# RTI-RoR.net
KiCad netlist of a schematic drawn in EAGLE
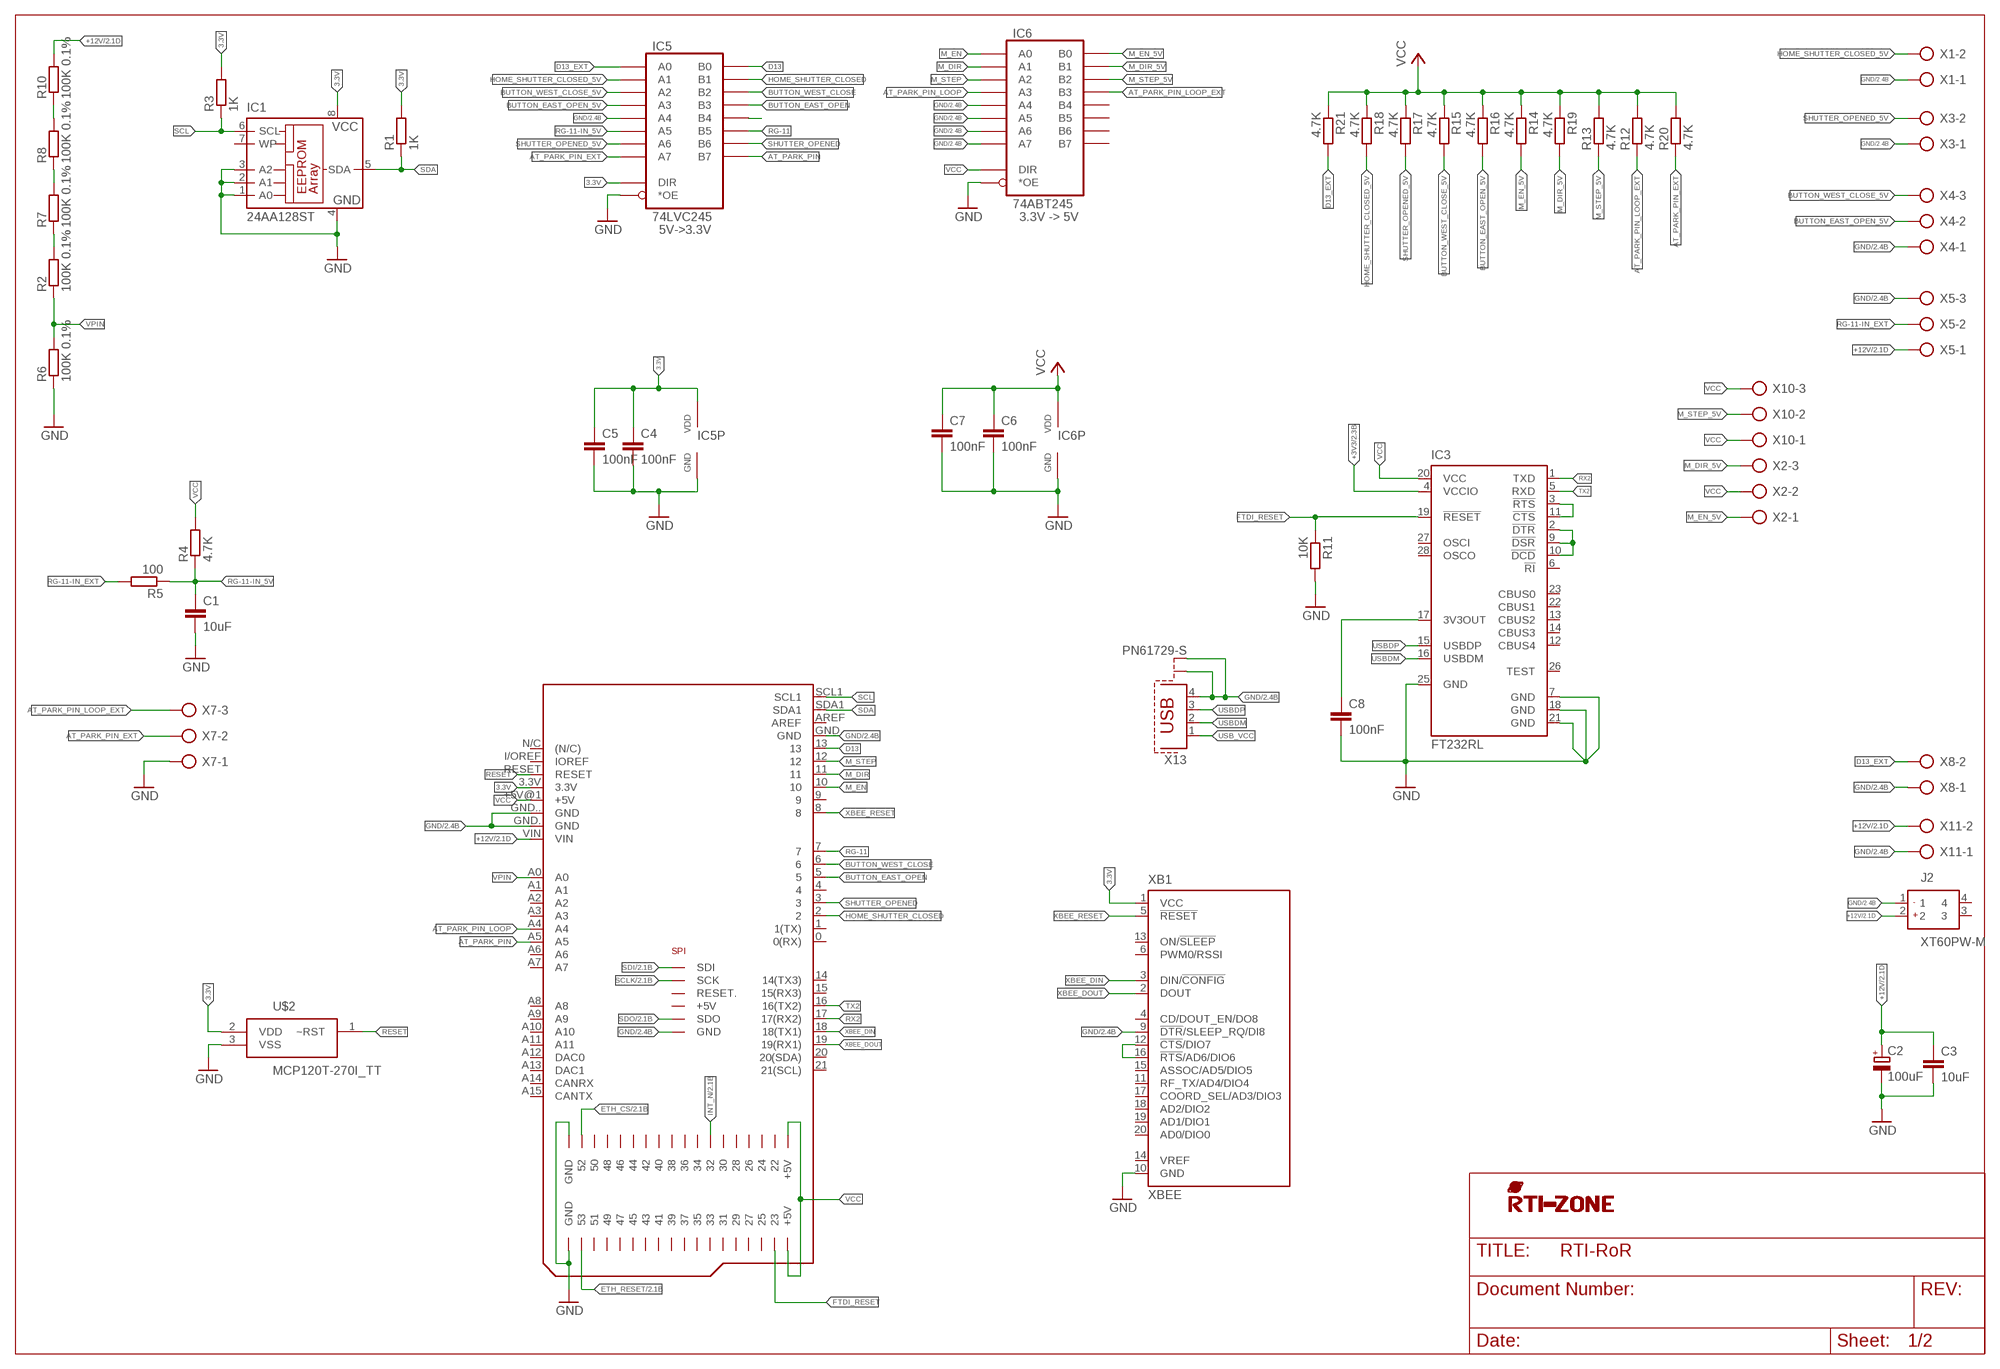
[diagram p0: schematic, sheet 1]
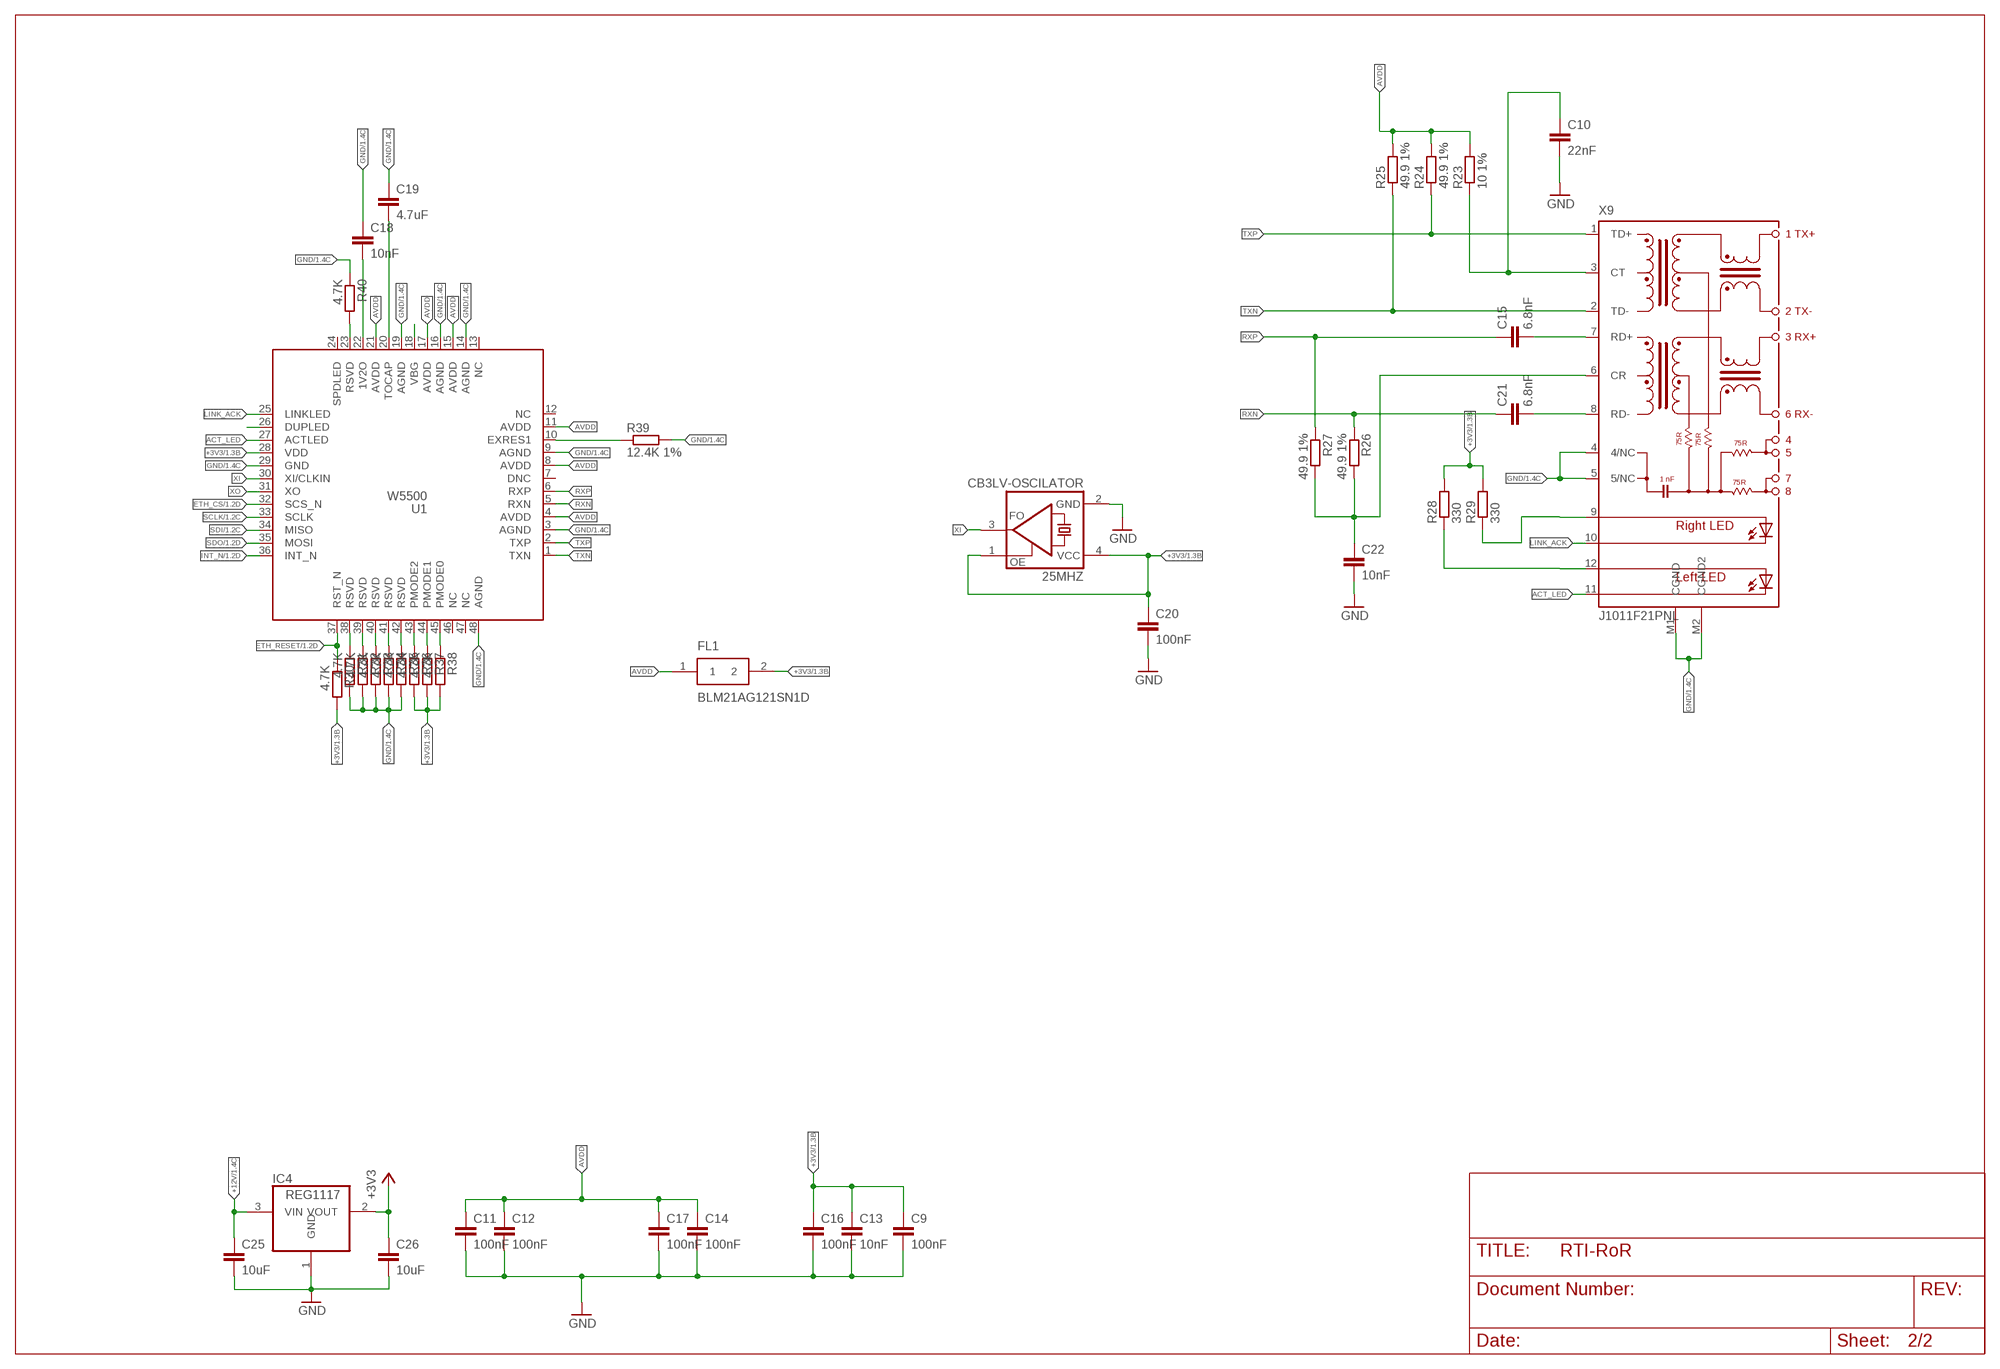
[diagram p1: schematic, sheet 2]

(export (version "E")
  (design (tool "Eeschema 10.0.6"))
  (components
    (comp (ref "C1")
      (value "10uF")
      (footprint "eagle-import:C0805")
      (fields (field (name "MPN") "CC0805KKX5R8BB106"))
      (libsource (lib "eagle-import") (part "C-EUC0805"))
    )
    (comp (ref "C2")
      (value "100uF")
      (footprint "eagle-import:UD-10X10_NICHICON")
      (fields (field (name "MPN") "MAL215099804E3"))
      (libsource (lib "eagle-import") (part "CPOL-EUUD-10X10"))
    )
    (comp (ref "C3")
      (value "10uF")
      (footprint "eagle-import:C0805")
      (fields (field (name "MPN") "CC0805KKX5R8BB106"))
      (libsource (lib "eagle-import") (part "C-EUC0805"))
    )
    (comp (ref "C4")
      (value "100nF")
      (footprint "eagle-import:C0805")
      (fields (field (name "MPN") "0805YD104KAT2A"))
      (libsource (lib "eagle-import") (part "C-EUC0805"))
    )
    (comp (ref "C5")
      (value "100nF")
      (footprint "eagle-import:C0805")
      (fields (field (name "MPN") "0805YD104KAT2A"))
      (libsource (lib "eagle-import") (part "C-EUC0805"))
    )
    (comp (ref "C6")
      (value "100nF")
      (footprint "eagle-import:C0805")
      (fields (field (name "MPN") "0805YD104KAT2A"))
      (libsource (lib "eagle-import") (part "C-EUC0805"))
    )
    (comp (ref "C7")
      (value "100nF")
      (footprint "eagle-import:C0805")
      (fields (field (name "MPN") "0805YD104KAT2A"))
      (libsource (lib "eagle-import") (part "C-EUC0805"))
    )
    (comp (ref "C8")
      (value "100nF")
      (footprint "eagle-import:C0805")
      (fields (field (name "MPN") "0805YD104KAT2A"))
      (libsource (lib "eagle-import") (part "C-EUC0805"))
    )
    (comp (ref "IC1")
      (value "24AA128ST")
      (footprint "eagle-import:TSSOP8")
      (fields (field (name "MF") "MICROCHIP") (field (name "MPN") "24AA128-I/ST"))
      (libsource (lib "eagle-import") (part "24STAA128"))
    )
    (comp (ref "IC3")
      (value "FT232RL")
      (footprint "eagle-import:SSOP28")
      (fields (field (name "MPN") "FT232RL-REEL"))
      (libsource (lib "eagle-import") (part "FT232RL"))
    )
    (comp (ref "IC5")
      (value "74LVC245")
      (footprint "eagle-import:TSSOP20")
      (fields (field (name "MPN") "74LVC245APW,112"))
      (libsource (lib "eagle-import") (part "74245LVC"))
    )
    (comp (ref "IC6")
      (value "74ABT245")
      (footprint "eagle-import:TSSOP20")
      (fields (field (name "MPN") "74ABT245PW,112"))
      (libsource (lib "eagle-import") (part "74245ABT"))
    )
    (comp (ref "J2")
      (value "XT60PW-M")
      (footprint "eagle-import:XT60PWM")
      (libsource (lib "eagle-import") (part "XT60PW-M"))
    )
    (comp (ref "R1")
      (value "1K")
      (footprint "eagle-import:R0805")
      (fields (field (name "MPN") "RT0805FRE071KL"))
      (libsource (lib "eagle-import") (part "R-EU_R0805"))
    )
    (comp (ref "R2")
      (value "100K 0.1%")
      (footprint "eagle-import:R0805")
      (fields (field (name "MPN") "AT0805BRD07100KL"))
      (libsource (lib "eagle-import") (part "R-EU_R0805"))
    )
    (comp (ref "R3")
      (value "1K")
      (footprint "eagle-import:R0805")
      (fields (field (name "MPN") "RT0805FRE071KL"))
      (libsource (lib "eagle-import") (part "R-EU_R0805"))
    )
    (comp (ref "R4")
      (value "4.7K")
      (footprint "eagle-import:R0805")
      (fields (field (name "MPN") "RT0805FRE074K7L"))
      (libsource (lib "eagle-import") (part "R-EU_R0805"))
    )
    (comp (ref "R5")
      (value "100")
      (footprint "eagle-import:R0805")
      (fields (field (name "MPN") "RT0805FRD07100RL"))
      (libsource (lib "eagle-import") (part "R-EU_R0805"))
    )
    (comp (ref "R6")
      (value "100K 0.1%")
      (footprint "eagle-import:R0805")
      (fields (field (name "MPN") "AT0805BRD07100KL"))
      (libsource (lib "eagle-import") (part "R-EU_R0805"))
    )
    (comp (ref "R7")
      (value "100K 0.1%")
      (footprint "eagle-import:R0805")
      (fields (field (name "MPN") "AT0805BRD07100KL"))
      (libsource (lib "eagle-import") (part "R-EU_R0805"))
    )
    (comp (ref "R8")
      (value "100K 0.1%")
      (footprint "eagle-import:R0805")
      (fields (field (name "MPN") "AT0805BRD07100KL"))
      (libsource (lib "eagle-import") (part "R-EU_R0805"))
    )
    (comp (ref "R10")
      (value "100K 0.1%")
      (footprint "eagle-import:R0805")
      (fields (field (name "MPN") "AT0805BRD07100KL"))
      (libsource (lib "eagle-import") (part "R-EU_R0805"))
    )
    (comp (ref "R11")
      (value "10K")
      (footprint "eagle-import:R0805")
      (fields (field (name "MPN") "RT0805FRE0710KL"))
      (libsource (lib "eagle-import") (part "R-EU_R0805"))
    )
    (comp (ref "R12")
      (value "4.7K")
      (footprint "eagle-import:R0805")
      (fields (field (name "MPN") "RT0805FRE074K7L"))
      (libsource (lib "eagle-import") (part "R-EU_R0805"))
    )
    (comp (ref "R13")
      (value "4.7K")
      (footprint "eagle-import:R0805")
      (fields (field (name "MPN") "RT0805FRE074K7L"))
      (libsource (lib "eagle-import") (part "R-EU_R0805"))
    )
    (comp (ref "R14")
      (value "4.7K")
      (footprint "eagle-import:R0805")
      (fields (field (name "MPN") "RT0805FRE074K7L"))
      (libsource (lib "eagle-import") (part "R-EU_R0805"))
    )
    (comp (ref "R15")
      (value "4.7K")
      (footprint "eagle-import:R0805")
      (fields (field (name "MPN") "RT0805FRE074K7L"))
      (libsource (lib "eagle-import") (part "R-EU_R0805"))
    )
    (comp (ref "R16")
      (value "4.7K")
      (footprint "eagle-import:R0805")
      (fields (field (name "MPN") "RT0805FRE074K7L"))
      (libsource (lib "eagle-import") (part "R-EU_R0805"))
    )
    (comp (ref "R17")
      (value "4.7K")
      (footprint "eagle-import:R0805")
      (fields (field (name "MPN") "RT0805FRE074K7L"))
      (libsource (lib "eagle-import") (part "R-EU_R0805"))
    )
    (comp (ref "R18")
      (value "4.7K")
      (footprint "eagle-import:R0805")
      (fields (field (name "MPN") "RT0805FRE074K7L"))
      (libsource (lib "eagle-import") (part "R-EU_R0805"))
    )
    (comp (ref "R19")
      (value "4.7K")
      (footprint "eagle-import:R0805")
      (fields (field (name "MPN") "RT0805FRE074K7L"))
      (libsource (lib "eagle-import") (part "R-EU_R0805"))
    )
    (comp (ref "R20")
      (value "4.7K")
      (footprint "eagle-import:R0805")
      (fields (field (name "MPN") "RT0805FRE074K7L"))
      (libsource (lib "eagle-import") (part "R-EU_R0805"))
    )
    (comp (ref "R21")
      (value "4.7K")
      (footprint "eagle-import:R0805")
      (fields (field (name "MPN") "RT0805FRE074K7L"))
      (libsource (lib "eagle-import") (part "R-EU_R0805"))
    )
    (comp (ref "U$1")
      (value "ARDUINO_DUE_SHIELD_FULL")
      (footprint "eagle-import:ARDUINO_DUE_SHIELD_FULL")
      (libsource (lib "eagle-import") (part "ARDUINO_DUE_SHIELD_FULL"))
    )
    (comp (ref "U$2")
      (value "MCP120T-270I_TT")
      (footprint "eagle-import:SOT95P237X112-3N")
      (fields
        (field (name "MANUFACTURER_PART_NUMBER") "MCP120T-270I/TT")
        (field (name "MOUSER_PART_NUMBER") "579-MCP120T-270I/TT")
      )
      (libsource (lib "eagle-import") (part "MCP120T-270I_TT"))
    )
    (comp (ref "U$4")
      (value "RTI-LOGO_BIG")
      (footprint "eagle-import:LOGO_BIG")
      (libsource (lib "eagle-import") (part "RTI-LOGO_BIG"))
    )
    (comp (ref "X1")
      (value "AK500/2")
      (footprint "eagle-import:AK500_2")
      (fields (field (name "MPN") "691101710002"))
      (libsource (lib "eagle-import") (part "AK500/2"))
    )
    (comp (ref "X2")
      (value "AK500/3")
      (footprint "eagle-import:AK500_3")
      (libsource (lib "eagle-import") (part "AK500/3"))
    )
    (comp (ref "X3")
      (value "AK500/2")
      (footprint "eagle-import:AK500_2")
      (fields (field (name "MPN") "691101710002"))
      (libsource (lib "eagle-import") (part "AK500/2"))
    )
    (comp (ref "X4")
      (value "AK500/3")
      (footprint "eagle-import:AK500_3")
      (fields (field (name "MPN") "691101710003"))
      (libsource (lib "eagle-import") (part "AK500/3"))
    )
    (comp (ref "X5")
      (value "AK500/3")
      (footprint "eagle-import:AK500_3")
      (fields (field (name "MPN") "691101710003"))
      (libsource (lib "eagle-import") (part "AK500/3"))
    )
    (comp (ref "X7")
      (value "AK500/3")
      (footprint "eagle-import:AK500_3")
      (fields (field (name "MPN") "691101710003"))
      (libsource (lib "eagle-import") (part "AK500/3"))
    )
    (comp (ref "X8")
      (value "AK500/2")
      (footprint "eagle-import:AK500_2")
      (fields (field (name "MPN") "691101710002"))
      (libsource (lib "eagle-import") (part "AK500/2"))
    )
    (comp (ref "X10")
      (value "AK500/3")
      (footprint "eagle-import:AK500_3")
      (libsource (lib "eagle-import") (part "AK500/3"))
    )
    (comp (ref "X11")
      (value "AK500/2")
      (footprint "eagle-import:AK500_2")
      (fields (field (name "MPN") "691101710002"))
      (libsource (lib "eagle-import") (part "AK500/2"))
    )
    (comp (ref "X13")
      (value "PN61729-S")
      (footprint "eagle-import:PN61729-S")
      (fields (field (name "MPN") "SS-52300-001"))
      (libsource (lib "eagle-import") (part "PN61729-S"))
    )
    (comp (ref "XB1")
      (value "XBEE")
      (footprint "eagle-import:XBEE")
      (fields (field (name "MPN") "XBP24-Z7UIT-004"))
      (libsource (lib "eagle-import") (part "XBEE"))
    )
    (comp (ref "25MHZ")
      (value "CB3LV-OSCILATOR")
      (footprint "eagle-import:SMD-7050_4P")
      (fields (field (name "MPN") "CB3LV-3I-25M0000"))
      (libsource (lib "eagle-import") (part "CB3LV-OSCILATOR"))
    )
    (comp (ref "C9")
      (value "100nF")
      (footprint "eagle-import:C0805")
      (fields (field (name "MPN") "0805YD104KAT2A"))
      (libsource (lib "eagle-import") (part "C-EUC0805"))
    )
    (comp (ref "C10")
      (value "22nF")
      (footprint "eagle-import:C0805")
      (fields (field (name "MPN") "CC0805JRX7R8BB223"))
      (libsource (lib "eagle-import") (part "C-EUC0805"))
    )
    (comp (ref "C11")
      (value "100nF")
      (footprint "eagle-import:C0805")
      (fields (field (name "MPN") "0805YD104KAT2A"))
      (libsource (lib "eagle-import") (part "C-EUC0805"))
    )
    (comp (ref "C12")
      (value "100nF")
      (footprint "eagle-import:C0805")
      (fields (field (name "MPN") "0805YD104KAT2A"))
      (libsource (lib "eagle-import") (part "C-EUC0805"))
    )
    (comp (ref "C13")
      (value "10nF")
      (footprint "eagle-import:C0805")
      (fields (field (name "MPN") " CC0805KRX7R9BB103"))
      (libsource (lib "eagle-import") (part "C-EUC0805"))
    )
    (comp (ref "C14")
      (value "100nF")
      (footprint "eagle-import:C0805")
      (fields (field (name "MPN") "0805YD104KAT2A"))
      (libsource (lib "eagle-import") (part "C-EUC0805"))
    )
    (comp (ref "C15")
      (value "6.8nF")
      (footprint "eagle-import:C0805")
      (fields (field (name "MPN") "C0805C682F4HACTU"))
      (libsource (lib "eagle-import") (part "C-EUC0805"))
    )
    (comp (ref "C16")
      (value "100nF")
      (footprint "eagle-import:C0805")
      (fields (field (name "MPN") "0805YD104KAT2A"))
      (libsource (lib "eagle-import") (part "C-EUC0805"))
    )
    (comp (ref "C17")
      (value "100nF")
      (footprint "eagle-import:C0805")
      (fields (field (name "MPN") "0805YD104KAT2A"))
      (libsource (lib "eagle-import") (part "C-EUC0805"))
    )
    (comp (ref "C18")
      (value "10nF")
      (footprint "eagle-import:C0805")
      (fields (field (name "MPN") " CC0805KRX7R9BB103"))
      (libsource (lib "eagle-import") (part "C-EUC0805"))
    )
    (comp (ref "C19")
      (value "4.7uF")
      (footprint "eagle-import:C0805")
      (fields (field (name "MPN") "C0805C475J3RACTU"))
      (libsource (lib "eagle-import") (part "C-EUC0805"))
    )
    (comp (ref "C20")
      (value "100nF")
      (footprint "eagle-import:C0805")
      (fields (field (name "MPN") "0805YD104KAT2A"))
      (libsource (lib "eagle-import") (part "C-EUC0805"))
    )
    (comp (ref "C21")
      (value "6.8nF")
      (footprint "eagle-import:C0805")
      (fields (field (name "MPN") "C0805C682F4HACTU"))
      (libsource (lib "eagle-import") (part "C-EUC0805"))
    )
    (comp (ref "C22")
      (value "10nF")
      (footprint "eagle-import:C0805")
      (fields (field (name "MPN") " CC0805KRX7R9BB103"))
      (libsource (lib "eagle-import") (part "C-EUC0805"))
    )
    (comp (ref "C25")
      (value "10uF")
      (footprint "eagle-import:C0805")
      (fields (field (name "MPN") "CC0805KKX5R8BB106"))
      (libsource (lib "eagle-import") (part "C-EUC0805"))
    )
    (comp (ref "C26")
      (value "10uF")
      (footprint "eagle-import:C0805")
      (fields (field (name "MPN") "CC0805KKX5R8BB106"))
      (libsource (lib "eagle-import") (part "C-EUC0805"))
    )
    (comp (ref "FL1")
      (value "BLM21AG121SN1D")
      (footprint "eagle-import:L0805")
      (libsource (lib "eagle-import") (part "BLM21AG121SN1D"))
    )
    (comp (ref "IC4")
      (value "REG1117")
      (footprint "eagle-import:SOT223")
      (fields (field (name "MPN") "REG1117-3.3/2K5"))
      (libsource (lib "eagle-import") (part "REG1117"))
    )
    (comp (ref "R23")
      (value "10 1%")
      (footprint "eagle-import:R0805")
      (fields (field (name "MPN") "RT0805FRE1310RL"))
      (libsource (lib "eagle-import") (part "R-EU_R0805"))
    )
    (comp (ref "R24")
      (value "49.9 1%")
      (footprint "eagle-import:R0805")
      (fields (field (name "MPN") "RC0805FR-0749R9L"))
      (libsource (lib "eagle-import") (part "R-EU_R0805"))
    )
    (comp (ref "R25")
      (value "49.9 1%")
      (footprint "eagle-import:R0805")
      (fields (field (name "MPN") "RC0805FR-0749R9L"))
      (libsource (lib "eagle-import") (part "R-EU_R0805"))
    )
    (comp (ref "R26")
      (value "49.9 1%")
      (footprint "eagle-import:R0805")
      (fields (field (name "MPN") "RC0805FR-0749R9L"))
      (libsource (lib "eagle-import") (part "R-EU_R0805"))
    )
    (comp (ref "R27")
      (value "49.9 1%")
      (footprint "eagle-import:R0805")
      (fields (field (name "MPN") "RC0805FR-0749R9L"))
      (libsource (lib "eagle-import") (part "R-EU_R0805"))
    )
    (comp (ref "R28")
      (value "330")
      (footprint "eagle-import:R0805")
      (fields (field (name "MPN") " RC0805JR-07330RL"))
      (libsource (lib "eagle-import") (part "R-EU_R0805"))
    )
    (comp (ref "R29")
      (value "330")
      (footprint "eagle-import:R0805")
      (fields (field (name "MPN") " RC0805JR-07330RL"))
      (libsource (lib "eagle-import") (part "R-EU_R0805"))
    )
    (comp (ref "R30")
      (value "4.7K")
      (footprint "eagle-import:R0805")
      (fields (field (name "MPN") "RT0805FRE074K7L"))
      (libsource (lib "eagle-import") (part "R-EU_R0805"))
    )
    (comp (ref "R31")
      (value "4.7K")
      (footprint "eagle-import:R0805")
      (fields (field (name "MPN") "RT0805FRE074K7L"))
      (libsource (lib "eagle-import") (part "R-EU_R0805"))
    )
    (comp (ref "R32")
      (value "4.7K")
      (footprint "eagle-import:R0805")
      (fields (field (name "MPN") "RT0805FRE074K7L"))
      (libsource (lib "eagle-import") (part "R-EU_R0805"))
    )
    (comp (ref "R33")
      (value "4.7K")
      (footprint "eagle-import:R0805")
      (fields (field (name "MPN") "RT0805FRE074K7L"))
      (libsource (lib "eagle-import") (part "R-EU_R0805"))
    )
    (comp (ref "R34")
      (value "4.7K")
      (footprint "eagle-import:R0805")
      (fields (field (name "MPN") "RT0805FRE074K7L"))
      (libsource (lib "eagle-import") (part "R-EU_R0805"))
    )
    (comp (ref "R35")
      (value "4.7K")
      (footprint "eagle-import:R0805")
      (fields (field (name "MPN") "RT0805FRE074K7L"))
      (libsource (lib "eagle-import") (part "R-EU_R0805"))
    )
    (comp (ref "R36")
      (value "4.7K")
      (footprint "eagle-import:R0805")
      (fields (field (name "MPN") "RT0805FRE074K7L"))
      (libsource (lib "eagle-import") (part "R-EU_R0805"))
    )
    (comp (ref "R37")
      (value "4.7K")
      (footprint "eagle-import:R0805")
      (fields (field (name "MPN") "RT0805FRE074K7L"))
      (libsource (lib "eagle-import") (part "R-EU_R0805"))
    )
    (comp (ref "R38")
      (value "4.7K")
      (footprint "eagle-import:R0805")
      (fields (field (name "MPN") "RT0805FRE074K7L"))
      (libsource (lib "eagle-import") (part "R-EU_R0805"))
    )
    (comp (ref "R39")
      (value "12.4K 1%")
      (footprint "eagle-import:R0805")
      (fields (field (name "MPN") "RC0805FR-0712K4L"))
      (libsource (lib "eagle-import") (part "R-EU_R0805"))
    )
    (comp (ref "R40")
      (value "4.7K")
      (footprint "eagle-import:R0805")
      (fields (field (name "MPN") "RT0805FRE074K7L"))
      (libsource (lib "eagle-import") (part "R-EU_R0805"))
    )
    (comp (ref "U1")
      (value "W5500")
      (footprint "eagle-import:LQFP48")
      (libsource (lib "eagle-import") (part "W5500"))
    )
    (comp (ref "X9")
      (value "J1011F21PNL")
      (footprint "eagle-import:J1011F21PNL")
      (fields (field (name "MPN") "J1011F21PNL"))
      (libsource (lib "eagle-import") (part "J1011F21PNL"))
    )
  )
  (nets
    (net (code "1") (name "+3V3") (class "Default")
      (node (ref "25MHZ") (pin "1") (pinfunction "OE_1") (pintype "input"))
      (node (ref "25MHZ") (pin "4") (pinfunction "VDD_4") (pintype "power_in"))
      (node (ref "C13") (pin "1") (pinfunction "1_1") (pintype "passive"))
      (node (ref "C16") (pin "1") (pinfunction "1_1") (pintype "passive"))
      (node (ref "C20") (pin "1") (pinfunction "1_1") (pintype "passive"))
      (node (ref "C26") (pin "1") (pinfunction "1_1") (pintype "passive"))
      (node (ref "C9") (pin "1") (pinfunction "1_1") (pintype "passive"))
      (node (ref "FL1") (pin "2") (pinfunction "2_2") (pintype "bidirectional"))
      (node (ref "IC3") (pin "4") (pinfunction "VCCIO_4") (pintype "power_in"))
      (node (ref "IC4") (pin "2") (pinfunction "VOUT_2") (pintype "output"))
      (node (ref "R28") (pin "2") (pinfunction "2_2") (pintype "passive"))
      (node (ref "R29") (pin "2") (pinfunction "2_2") (pintype "passive"))
      (node (ref "R30") (pin "2") (pinfunction "2_2") (pintype "passive"))
      (node (ref "R36") (pin "2") (pinfunction "2_2") (pintype "passive"))
      (node (ref "R37") (pin "2") (pinfunction "2_2") (pintype "passive"))
      (node (ref "R38") (pin "2") (pinfunction "2_2") (pintype "passive"))
      (node (ref "U1") (pin "28") (pinfunction "VDD_28") (pintype "passive"))
    )
    (net (code "2") (name "+5V") (class "Default")
      (node (ref "U$1") (pin "+5V@2") (pinfunction "+5V_+5V@2") (pintype "power_in"))
    )
    (net (code "3") (name "+12V") (class "Default")
      (node (ref "C2") (pin "+") (pinfunction "+_+") (pintype "passive"))
      (node (ref "C25") (pin "1") (pinfunction "1_1") (pintype "passive"))
      (node (ref "C3") (pin "1") (pinfunction "1_1") (pintype "passive"))
      (node (ref "IC4") (pin "3") (pinfunction "VIN_3") (pintype "input"))
      (node (ref "J2") (pin "2") (pinfunction "2_2") (pintype "bidirectional"))
      (node (ref "R10") (pin "2") (pinfunction "2_2") (pintype "passive"))
      (node (ref "U$1") (pin "VIN") (pinfunction "VIN_VIN") (pintype "power_in"))
      (node (ref "X11") (pin "2") (pinfunction "KL_2") (pintype "passive"))
      (node (ref "X5") (pin "1") (pinfunction "KL_1") (pintype "passive"))
    )
    (net (code "4") (name "3.3V") (class "Default")
      (node (ref "C4") (pin "1") (pinfunction "1_1") (pintype "passive"))
      (node (ref "C5") (pin "1") (pinfunction "1_1") (pintype "passive"))
      (node (ref "IC1") (pin "8") (pinfunction "VCC_8") (pintype "power_in"))
      (node (ref "IC5") (pin "P$1") (pinfunction "DIR_P$1") (pintype "input"))
      (node (ref "IC5") (pin "P$20") (pinfunction "VDD_P$20") (pintype "power_in"))
      (node (ref "R1") (pin "2") (pinfunction "2_2") (pintype "passive"))
      (node (ref "R3") (pin "2") (pinfunction "2_2") (pintype "passive"))
      (node (ref "U$1") (pin "3.3V") (pinfunction "3.3V_3.3V") (pintype "power_in"))
      (node (ref "U$2") (pin "2") (pinfunction "VDD_2") (pintype "bidirectional"))
      (node (ref "XB1") (pin "1") (pinfunction "VCC_1") (pintype "power_in"))
    )
    (net (code "5") (name "ACT_LED") (class "Default")
      (node (ref "U1") (pin "27") (pinfunction "ACTLED_27") (pintype "passive"))
      (node (ref "X9") (pin "11") (pinfunction "C-L_11") (pintype "passive"))
    )
    (net (code "6") (name "AT_PARK_PIN") (class "Default")
      (node (ref "IC5") (pin "P$11") (pinfunction "B7_P$11") (pintype "bidirectional"))
      (node (ref "U$1") (pin "A5") (pinfunction "A5_A5") (pintype "bidirectional"))
    )
    (net (code "7") (name "AT_PARK_PIN_EXT") (class "Default")
      (node (ref "IC5") (pin "P$9") (pinfunction "A7_P$9") (pintype "bidirectional"))
      (node (ref "R20") (pin "1") (pinfunction "1_1") (pintype "passive"))
      (node (ref "X7") (pin "2") (pinfunction "KL_2") (pintype "passive"))
    )
    (net (code "8") (name "AT_PARK_PIN_LOOP") (class "Default")
      (node (ref "IC6") (pin "P$5") (pinfunction "A3_P$5") (pintype "bidirectional"))
      (node (ref "U$1") (pin "A4") (pinfunction "A4_A4") (pintype "bidirectional"))
    )
    (net (code "9") (name "AT_PARK_PIN_LOOP_EXT") (class "Default")
      (node (ref "IC6") (pin "P$15") (pinfunction "B3_P$15") (pintype "bidirectional"))
      (node (ref "R12") (pin "1") (pinfunction "1_1") (pintype "passive"))
      (node (ref "X7") (pin "3") (pinfunction "KL_3") (pintype "passive"))
    )
    (net (code "10") (name "AVDD") (class "Default")
      (node (ref "C11") (pin "1") (pinfunction "1_1") (pintype "passive"))
      (node (ref "C12") (pin "1") (pinfunction "1_1") (pintype "passive"))
      (node (ref "C14") (pin "1") (pinfunction "1_1") (pintype "passive"))
      (node (ref "C17") (pin "1") (pinfunction "1_1") (pintype "passive"))
      (node (ref "FL1") (pin "1") (pinfunction "1_1") (pintype "bidirectional"))
      (node (ref "R23") (pin "2") (pinfunction "2_2") (pintype "passive"))
      (node (ref "R24") (pin "2") (pinfunction "2_2") (pintype "passive"))
      (node (ref "R25") (pin "2") (pinfunction "2_2") (pintype "passive"))
      (node (ref "U1") (pin "11") (pinfunction "AVDD_11") (pintype "passive"))
      (node (ref "U1") (pin "15") (pinfunction "AVDD_15") (pintype "passive"))
      (node (ref "U1") (pin "17") (pinfunction "AVDD_17") (pintype "passive"))
      (node (ref "U1") (pin "21") (pinfunction "AVDD_21") (pintype "passive"))
      (node (ref "U1") (pin "4") (pinfunction "AVDD_4") (pintype "passive"))
      (node (ref "U1") (pin "8") (pinfunction "AVDD_8") (pintype "passive"))
    )
    (net (code "11") (name "BUTTON_EAST_OPEN") (class "Default")
      (node (ref "IC5") (pin "P$15") (pinfunction "B3_P$15") (pintype "bidirectional"))
      (node (ref "U$1") (pin "5") (pinfunction "5_5") (pintype "bidirectional"))
    )
    (net (code "12") (name "BUTTON_EAST_OPEN_5V") (class "Default")
      (node (ref "IC5") (pin "P$5") (pinfunction "A3_P$5") (pintype "bidirectional"))
      (node (ref "R16") (pin "2") (pinfunction "2_2") (pintype "passive"))
      (node (ref "X4") (pin "2") (pinfunction "KL_2") (pintype "passive"))
    )
    (net (code "13") (name "BUTTON_WEST_CLOSE") (class "Default")
      (node (ref "IC5") (pin "P$16") (pinfunction "B2_P$16") (pintype "bidirectional"))
      (node (ref "U$1") (pin "6") (pinfunction "6_6") (pintype "bidirectional"))
    )
    (net (code "14") (name "BUTTON_WEST_CLOSE_5V") (class "Default")
      (node (ref "IC5") (pin "P$4") (pinfunction "A2_P$4") (pintype "bidirectional"))
      (node (ref "R15") (pin "2") (pinfunction "2_2") (pintype "passive"))
      (node (ref "X4") (pin "3") (pinfunction "KL_3") (pintype "passive"))
    )
    (net (code "15") (name "D13") (class "Default")
      (node (ref "IC5") (pin "P$18") (pinfunction "B0_P$18") (pintype "bidirectional"))
      (node (ref "U$1") (pin "13") (pinfunction "13_13") (pintype "bidirectional"))
    )
    (net (code "16") (name "D13_EXT") (class "Default")
      (node (ref "IC5") (pin "P$2") (pinfunction "A0_P$2") (pintype "bidirectional"))
      (node (ref "R21") (pin "2") (pinfunction "2_2") (pintype "passive"))
      (node (ref "X8") (pin "2") (pinfunction "KL_2") (pintype "passive"))
    )
    (net (code "17") (name "ETH_CS") (class "Default")
      (node (ref "U$1") (pin "52") (pinfunction "52_52") (pintype "bidirectional"))
      (node (ref "U1") (pin "32") (pinfunction "SCS_N_32") (pintype "passive"))
    )
    (net (code "18") (name "ETH_RESET") (class "Default")
      (node (ref "R30") (pin "1") (pinfunction "1_1") (pintype "passive"))
      (node (ref "U$1") (pin "53") (pinfunction "53_53") (pintype "bidirectional"))
      (node (ref "U1") (pin "37") (pinfunction "RST_N_37") (pintype "passive"))
    )
    (net (code "19") (name "FTDI_RESET") (class "Default")
      (node (ref "IC3") (pin "19") (pinfunction "~{RESET}_19") (pintype "input"))
      (node (ref "R11") (pin "1") (pinfunction "1_1") (pintype "passive"))
      (node (ref "U$1") (pin "23") (pinfunction "23_23") (pintype "bidirectional"))
    )
    (net (code "20") (name "GND") (class "Default")
      (node (ref "25MHZ") (pin "2") (pinfunction "GND_2") (pintype "power_in"))
      (node (ref "C1") (pin "2") (pinfunction "2_2") (pintype "passive"))
      (node (ref "C10") (pin "2") (pinfunction "2_2") (pintype "passive"))
      (node (ref "C11") (pin "2") (pinfunction "2_2") (pintype "passive"))
      (node (ref "C12") (pin "2") (pinfunction "2_2") (pintype "passive"))
      (node (ref "C13") (pin "2") (pinfunction "2_2") (pintype "passive"))
      (node (ref "C14") (pin "2") (pinfunction "2_2") (pintype "passive"))
      (node (ref "C16") (pin "2") (pinfunction "2_2") (pintype "passive"))
      (node (ref "C17") (pin "2") (pinfunction "2_2") (pintype "passive"))
      (node (ref "C18") (pin "1") (pinfunction "1_1") (pintype "passive"))
      (node (ref "C19") (pin "1") (pinfunction "1_1") (pintype "passive"))
      (node (ref "C2") (pin "-") (pinfunction "-_-") (pintype "passive"))
      (node (ref "C20") (pin "2") (pinfunction "2_2") (pintype "passive"))
      (node (ref "C22") (pin "2") (pinfunction "2_2") (pintype "passive"))
      (node (ref "C25") (pin "2") (pinfunction "2_2") (pintype "passive"))
      (node (ref "C26") (pin "2") (pinfunction "2_2") (pintype "passive"))
      (node (ref "C3") (pin "2") (pinfunction "2_2") (pintype "passive"))
      (node (ref "C4") (pin "2") (pinfunction "2_2") (pintype "passive"))
      (node (ref "C5") (pin "2") (pinfunction "2_2") (pintype "passive"))
      (node (ref "C6") (pin "2") (pinfunction "2_2") (pintype "passive"))
      (node (ref "C7") (pin "2") (pinfunction "2_2") (pintype "passive"))
      (node (ref "C8") (pin "2") (pinfunction "2_2") (pintype "passive"))
      (node (ref "C9") (pin "2") (pinfunction "2_2") (pintype "passive"))
      (node (ref "IC1") (pin "1") (pinfunction "A0_1") (pintype "input"))
      (node (ref "IC1") (pin "2") (pinfunction "A1_2") (pintype "input"))
      (node (ref "IC1") (pin "3") (pinfunction "A2_3") (pintype "input"))
      (node (ref "IC1") (pin "4") (pinfunction "GND_4") (pintype "power_in"))
      (node (ref "IC3") (pin "18") (pinfunction "GND_18") (pintype "power_in"))
      (node (ref "IC3") (pin "21") (pinfunction "GND_21") (pintype "power_in"))
      (node (ref "IC3") (pin "25") (pinfunction "GND_25") (pintype "power_in"))
      (node (ref "IC3") (pin "7") (pinfunction "GND_7") (pintype "power_in"))
      (node (ref "IC4") (pin "1") (pinfunction "GND_1") (pintype "power_in"))
      (node (ref "IC5") (pin "P$10") (pinfunction "GND_P$10") (pintype "power_in"))
      (node (ref "IC5") (pin "P$19") (pinfunction "*OE_P$19") (pintype "input"))
      (node (ref "IC5") (pin "P$6") (pinfunction "A4_P$6") (pintype "bidirectional"))
      (node (ref "IC6") (pin "P$10") (pinfunction "GND_P$10") (pintype "power_in"))
      (node (ref "IC6") (pin "P$19") (pinfunction "*OE_P$19") (pintype "input"))
      (node (ref "IC6") (pin "P$6") (pinfunction "A4_P$6") (pintype "bidirectional"))
      (node (ref "IC6") (pin "P$7") (pinfunction "A5_P$7") (pintype "bidirectional"))
      (node (ref "IC6") (pin "P$8") (pinfunction "A6_P$8") (pintype "bidirectional"))
      (node (ref "IC6") (pin "P$9") (pinfunction "A7_P$9") (pintype "bidirectional"))
      (node (ref "J2") (pin "1") (pinfunction "1_1") (pintype "bidirectional"))
      (node (ref "R11") (pin "2") (pinfunction "2_2") (pintype "passive"))
      (node (ref "R31") (pin "2") (pinfunction "2_2") (pintype "passive"))
      (node (ref "R32") (pin "2") (pinfunction "2_2") (pintype "passive"))
      (node (ref "R33") (pin "2") (pinfunction "2_2") (pintype "passive"))
      (node (ref "R34") (pin "2") (pinfunction "2_2") (pintype "passive"))
      (node (ref "R35") (pin "2") (pinfunction "2_2") (pintype "passive"))
      (node (ref "R39") (pin "2") (pinfunction "2_2") (pintype "passive"))
      (node (ref "R40") (pin "1") (pinfunction "1_1") (pintype "passive"))
      (node (ref "R6") (pin "1") (pinfunction "1_1") (pintype "passive"))
      (node (ref "U$1") (pin "GND") (pinfunction "GND_GND") (pintype "power_in"))
      (node (ref "U$1") (pin "GND.") (pinfunction "GND_GND.") (pintype "power_in"))
      (node (ref "U$1") (pin "GND..") (pinfunction "GND_GND..") (pintype "power_in"))
      (node (ref "U$1") (pin "GND...") (pinfunction "GND_GND...") (pintype "power_in"))
      (node (ref "U$1") (pin "GND....") (pinfunction "GND_GND....") (pintype "power_in"))
      (node (ref "U$1") (pin "GND__") (pinfunction "GND_GND__") (pintype "power_in"))
      (node (ref "U$2") (pin "3") (pinfunction "VSS_3") (pintype "bidirectional"))
      (node (ref "U1") (pin "14") (pinfunction "AGND_14") (pintype "passive"))
      (node (ref "U1") (pin "16") (pinfunction "AGND_16") (pintype "passive"))
      (node (ref "U1") (pin "19") (pinfunction "AGND_19") (pintype "passive"))
      (node (ref "U1") (pin "29") (pinfunction "GND_29") (pintype "passive"))
      (node (ref "U1") (pin "3") (pinfunction "AGND_3") (pintype "passive"))
      (node (ref "U1") (pin "48") (pinfunction "AGND_48") (pintype "passive"))
      (node (ref "U1") (pin "9") (pinfunction "AGND_9") (pintype "passive"))
      (node (ref "X1") (pin "1") (pinfunction "KL_1") (pintype "passive"))
      (node (ref "X11") (pin "1") (pinfunction "KL_1") (pintype "passive"))
      (node (ref "X13") (pin "4") (pinfunction "4_4") (pintype "passive"))
      (node (ref "X13") (pin "S1") (pinfunction "S1_S1") (pintype "passive"))
      (node (ref "X13") (pin "S2") (pinfunction "S2_S2") (pintype "passive"))
      (node (ref "X3") (pin "1") (pinfunction "KL_1") (pintype "passive"))
      (node (ref "X4") (pin "1") (pinfunction "KL_1") (pintype "passive"))
      (node (ref "X5") (pin "3") (pinfunction "KL_3") (pintype "passive"))
      (node (ref "X7") (pin "1") (pinfunction "KL_1") (pintype "passive"))
      (node (ref "X8") (pin "1") (pinfunction "KL_1") (pintype "passive"))
      (node (ref "X9") (pin "4") (pinfunction "4/NC_4") (pintype "input"))
      (node (ref "X9") (pin "5") (pinfunction "5/NC_5") (pintype "input"))
      (node (ref "X9") (pin "M1") (pinfunction "CGND_M1") (pintype "bidirectional"))
      (node (ref "X9") (pin "M2") (pinfunction "CGND2_M2") (pintype "bidirectional"))
      (node (ref "XB1") (pin "10") (pinfunction "GND_10") (pintype "power_in"))
      (node (ref "XB1") (pin "9") (pinfunction "~{DTR}/SLEEP_RQ/DI8_9") (pintype "bidirectional"))
    )
    (net (code "21") (name "HOME_SHUTTER_CLOSED") (class "Default")
      (node (ref "IC5") (pin "P$17") (pinfunction "B1_P$17") (pintype "bidirectional"))
      (node (ref "U$1") (pin "2") (pinfunction "2_2") (pintype "bidirectional"))
    )
    (net (code "22") (name "HOME_SHUTTER_CLOSED_5V") (class "Default")
      (node (ref "IC5") (pin "P$3") (pinfunction "A1_P$3") (pintype "bidirectional"))
      (node (ref "R18") (pin "2") (pinfunction "2_2") (pintype "passive"))
      (node (ref "X1") (pin "2") (pinfunction "KL_2") (pintype "passive"))
    )
    (net (code "23") (name "INT_N") (class "Default")
      (node (ref "U$1") (pin "32") (pinfunction "32_32") (pintype "bidirectional"))
      (node (ref "U1") (pin "36") (pinfunction "INT_N_36") (pintype "passive"))
    )
    (net (code "24") (name "LINK_ACK") (class "Default")
      (node (ref "U1") (pin "25") (pinfunction "LINKLED_25") (pintype "passive"))
      (node (ref "X9") (pin "10") (pinfunction "C-R_10") (pintype "passive"))
    )
    (net (code "25") (name "M_DIR") (class "Default")
      (node (ref "IC6") (pin "P$3") (pinfunction "A1_P$3") (pintype "bidirectional"))
      (node (ref "U$1") (pin "11") (pinfunction "11_11") (pintype "bidirectional"))
    )
    (net (code "26") (name "M_DIR_5V") (class "Default")
      (node (ref "IC6") (pin "P$17") (pinfunction "B1_P$17") (pintype "bidirectional"))
      (node (ref "R19") (pin "2") (pinfunction "2_2") (pintype "passive"))
      (node (ref "X2") (pin "3") (pinfunction "KL_3") (pintype "passive"))
    )
    (net (code "27") (name "M_EN") (class "Default")
      (node (ref "IC6") (pin "P$2") (pinfunction "A0_P$2") (pintype "bidirectional"))
      (node (ref "U$1") (pin "10") (pinfunction "10_10") (pintype "bidirectional"))
    )
    (net (code "28") (name "M_EN_5V") (class "Default")
      (node (ref "IC6") (pin "P$18") (pinfunction "B0_P$18") (pintype "bidirectional"))
      (node (ref "R14") (pin "2") (pinfunction "2_2") (pintype "passive"))
      (node (ref "X2") (pin "1") (pinfunction "KL_1") (pintype "passive"))
    )
    (net (code "29") (name "M_STEP") (class "Default")
      (node (ref "IC6") (pin "P$4") (pinfunction "A2_P$4") (pintype "bidirectional"))
      (node (ref "U$1") (pin "12") (pinfunction "12_12") (pintype "bidirectional"))
    )
    (net (code "30") (name "M_STEP_5V") (class "Default")
      (node (ref "IC6") (pin "P$16") (pinfunction "B2_P$16") (pintype "bidirectional"))
      (node (ref "R13") (pin "1") (pinfunction "1_1") (pintype "passive"))
      (node (ref "X10") (pin "2") (pinfunction "KL_2") (pintype "passive"))
    )
    (net (code "31") (name "Net-(IC3-3V3OUT)") (class "Default")
      (node (ref "C8") (pin "1") (pinfunction "1_1") (pintype "passive"))
      (node (ref "IC3") (pin "17") (pinfunction "3V3OUT_17") (pintype "output"))
    )
    (net (code "32") (name "Net-(IC3-~{CTS})") (class "Default")
      (node (ref "IC3") (pin "11") (pinfunction "~{CTS}_11") (pintype "input"))
      (node (ref "IC3") (pin "3") (pinfunction "~{RTS}_3") (pintype "output"))
    )
    (net (code "33") (name "Net-(IC3-~{DCD})") (class "Default")
      (node (ref "IC3") (pin "10") (pinfunction "~{DCD}_10") (pintype "input"))
      (node (ref "IC3") (pin "2") (pinfunction "~{DTR}_2") (pintype "output"))
      (node (ref "IC3") (pin "9") (pinfunction "~{DSR}_9") (pintype "input"))
    )
    (net (code "34") (name "Net-(R2-Pad2)") (class "Default")
      (node (ref "R2") (pin "2") (pinfunction "2_2") (pintype "passive"))
      (node (ref "R7") (pin "1") (pinfunction "1_1") (pintype "passive"))
    )
    (net (code "35") (name "Net-(R7-Pad2)") (class "Default")
      (node (ref "R7") (pin "2") (pinfunction "2_2") (pintype "passive"))
      (node (ref "R8") (pin "1") (pinfunction "1_1") (pintype "passive"))
    )
    (net (code "36") (name "Net-(R10-Pad1)") (class "Default")
      (node (ref "R10") (pin "1") (pinfunction "1_1") (pintype "passive"))
      (node (ref "R8") (pin "2") (pinfunction "2_2") (pintype "passive"))
    )
    (net (code "37") (name "Net-(R31-Pad1)") (class "Default")
      (node (ref "R31") (pin "1") (pinfunction "1_1") (pintype "passive"))
      (node (ref "U1") (pin "38") (pinfunction "RSVD_38") (pintype "passive"))
    )
    (net (code "38") (name "Net-(R32-Pad1)") (class "Default")
      (node (ref "R32") (pin "1") (pinfunction "1_1") (pintype "passive"))
      (node (ref "U1") (pin "39") (pinfunction "RSVD_39") (pintype "passive"))
    )
    (net (code "39") (name "Net-(R33-Pad1)") (class "Default")
      (node (ref "R33") (pin "1") (pinfunction "1_1") (pintype "passive"))
      (node (ref "U1") (pin "40") (pinfunction "RSVD_40") (pintype "passive"))
    )
    (net (code "40") (name "Net-(R34-Pad1)") (class "Default")
      (node (ref "R34") (pin "1") (pinfunction "1_1") (pintype "passive"))
      (node (ref "U1") (pin "41") (pinfunction "RSVD_41") (pintype "passive"))
    )
    (net (code "41") (name "Net-(R35-Pad1)") (class "Default")
      (node (ref "R35") (pin "1") (pinfunction "1_1") (pintype "passive"))
      (node (ref "U1") (pin "42") (pinfunction "RSVD_42") (pintype "passive"))
    )
    (net (code "42") (name "Net-(R40-Pad2)") (class "Default")
      (node (ref "R40") (pin "2") (pinfunction "2_2") (pintype "passive"))
      (node (ref "U1") (pin "23") (pinfunction "RSVD_23") (pintype "passive"))
    )
    (net (code "43") (name "Net-(U1-1V2O)") (class "Default")
      (node (ref "C18") (pin "2") (pinfunction "2_2") (pintype "passive"))
      (node (ref "U1") (pin "22") (pinfunction "1V2O_22") (pintype "passive"))
    )
    (net (code "44") (name "Net-(U1-EXRES1)") (class "Default")
      (node (ref "R39") (pin "1") (pinfunction "1_1") (pintype "passive"))
      (node (ref "U1") (pin "10") (pinfunction "EXRES1_10") (pintype "passive"))
    )
    (net (code "45") (name "Net-(U1-PMODE0)") (class "Default")
      (node (ref "R38") (pin "1") (pinfunction "1_1") (pintype "passive"))
      (node (ref "U1") (pin "45") (pinfunction "PMODE0_45") (pintype "passive"))
    )
    (net (code "46") (name "Net-(U1-PMODE1)") (class "Default")
      (node (ref "R37") (pin "1") (pinfunction "1_1") (pintype "passive"))
      (node (ref "U1") (pin "44") (pinfunction "PMODE1_44") (pintype "passive"))
    )
    (net (code "47") (name "Net-(U1-PMODE2)") (class "Default")
      (node (ref "R36") (pin "1") (pinfunction "1_1") (pintype "passive"))
      (node (ref "U1") (pin "43") (pinfunction "PMODE2_43") (pintype "passive"))
    )
    (net (code "48") (name "Net-(U1-TOCAP)") (class "Default")
      (node (ref "C19") (pin "2") (pinfunction "2_2") (pintype "passive"))
      (node (ref "U1") (pin "20") (pinfunction "TOCAP_20") (pintype "passive"))
    )
    (net (code "49") (name "Net-(X9-A-R)") (class "Default")
      (node (ref "R29") (pin "1") (pinfunction "1_1") (pintype "passive"))
      (node (ref "X9") (pin "9") (pinfunction "A-R_9") (pintype "passive"))
    )
    (net (code "50") (name "Net-(X9-AL)") (class "Default")
      (node (ref "R28") (pin "1") (pinfunction "1_1") (pintype "passive"))
      (node (ref "X9") (pin "12") (pinfunction "AL_12") (pintype "passive"))
    )
    (net (code "51") (name "Net-(X9-CR)") (class "Default")
      (node (ref "C22") (pin "1") (pinfunction "1_1") (pintype "passive"))
      (node (ref "R26") (pin "2") (pinfunction "2_2") (pintype "passive"))
      (node (ref "R27") (pin "2") (pinfunction "2_2") (pintype "passive"))
      (node (ref "X9") (pin "6") (pinfunction "CR_6") (pintype "input"))
    )
    (net (code "52") (name "Net-(X9-CT)") (class "Default")
      (node (ref "C10") (pin "1") (pinfunction "1_1") (pintype "passive"))
      (node (ref "R23") (pin "1") (pinfunction "1_1") (pintype "passive"))
      (node (ref "X9") (pin "3") (pinfunction "CT_3") (pintype "input"))
    )
    (net (code "53") (name "Net-(X9-RD+)") (class "Default")
      (node (ref "C15") (pin "2") (pinfunction "2_2") (pintype "passive"))
      (node (ref "X9") (pin "7") (pinfunction "RD+_7") (pintype "input"))
    )
    (net (code "54") (name "Net-(X9-RD-)") (class "Default")
      (node (ref "C21") (pin "2") (pinfunction "2_2") (pintype "passive"))
      (node (ref "X9") (pin "8") (pinfunction "RD-_8") (pintype "input"))
    )
    (net (code "55") (name "Net-(XB1-~{CTS}{slash}DIO7)") (class "Default")
      (node (ref "XB1") (pin "12") (pinfunction "~{CTS}/DIO7_12") (pintype "bidirectional"))
      (node (ref "XB1") (pin "16") (pinfunction "~{RTS}/AD6/DIO6_16") (pintype "bidirectional"))
    )
    (net (code "56") (name "RESET") (class "Default")
      (node (ref "U$1") (pin "RESET") (pinfunction "RESET_RESET") (pintype "bidirectional"))
      (node (ref "U$2") (pin "1") (pinfunction "~{RST}_1") (pintype "bidirectional"))
    )
    (net (code "57") (name "RG-11") (class "Default")
      (node (ref "IC5") (pin "P$13") (pinfunction "B5_P$13") (pintype "bidirectional"))
      (node (ref "U$1") (pin "7") (pinfunction "7_7") (pintype "bidirectional"))
    )
    (net (code "58") (name "RG-11-IN_5V") (class "Default")
      (node (ref "C1") (pin "1") (pinfunction "1_1") (pintype "passive"))
      (node (ref "IC5") (pin "P$7") (pinfunction "A5_P$7") (pintype "bidirectional"))
      (node (ref "R4") (pin "1") (pinfunction "1_1") (pintype "passive"))
      (node (ref "R5") (pin "1") (pinfunction "1_1") (pintype "passive"))
    )
    (net (code "59") (name "RG-11-IN_EXT") (class "Default")
      (node (ref "R5") (pin "2") (pinfunction "2_2") (pintype "passive"))
      (node (ref "X5") (pin "2") (pinfunction "KL_2") (pintype "passive"))
    )
    (net (code "60") (name "RX2") (class "Default")
      (node (ref "IC3") (pin "1") (pinfunction "TXD_1") (pintype "output"))
      (node (ref "U$1") (pin "17") (pinfunction "17(RX2)_17") (pintype "bidirectional"))
    )
    (net (code "61") (name "RXN") (class "Default")
      (node (ref "C21") (pin "1") (pinfunction "1_1") (pintype "passive"))
      (node (ref "R26") (pin "1") (pinfunction "1_1") (pintype "passive"))
      (node (ref "U1") (pin "5") (pinfunction "RXN_5") (pintype "passive"))
    )
    (net (code "62") (name "RXP") (class "Default")
      (node (ref "C15") (pin "1") (pinfunction "1_1") (pintype "passive"))
      (node (ref "R27") (pin "1") (pinfunction "1_1") (pintype "passive"))
      (node (ref "U1") (pin "6") (pinfunction "RXP_6") (pintype "passive"))
    )
    (net (code "63") (name "SCL") (class "Default")
      (node (ref "IC1") (pin "6") (pinfunction "SCL_6") (pintype "input"))
      (node (ref "R3") (pin "1") (pinfunction "1_1") (pintype "passive"))
      (node (ref "U$1") (pin "SCL1") (pinfunction "SCL1_SCL1") (pintype "bidirectional"))
    )
    (net (code "64") (name "SCLK") (class "Default")
      (node (ref "U$1") (pin "SCK") (pinfunction "SCK_SCK") (pintype "bidirectional"))
      (node (ref "U1") (pin "33") (pinfunction "SCLK_33") (pintype "passive"))
    )
    (net (code "65") (name "SDA") (class "Default")
      (node (ref "IC1") (pin "5") (pinfunction "SDA_5") (pintype "bidirectional"))
      (node (ref "R1") (pin "1") (pinfunction "1_1") (pintype "passive"))
      (node (ref "U$1") (pin "SDA1") (pinfunction "SDA1_SDA1") (pintype "bidirectional"))
    )
    (net (code "66") (name "SDI") (class "Default")
      (node (ref "U$1") (pin "MISO") (pinfunction "SDI_MISO") (pintype "bidirectional"))
      (node (ref "U1") (pin "34") (pinfunction "MISO_34") (pintype "passive"))
    )
    (net (code "67") (name "SDO") (class "Default")
      (node (ref "U$1") (pin "MOSI") (pinfunction "SDO_MOSI") (pintype "bidirectional"))
      (node (ref "U1") (pin "35") (pinfunction "MOSI_35") (pintype "passive"))
    )
    (net (code "68") (name "SHUTTER_OPENED") (class "Default")
      (node (ref "IC5") (pin "P$12") (pinfunction "B6_P$12") (pintype "bidirectional"))
      (node (ref "U$1") (pin "3") (pinfunction "3_3") (pintype "bidirectional"))
    )
    (net (code "69") (name "SHUTTER_OPENED_5V") (class "Default")
      (node (ref "IC5") (pin "P$8") (pinfunction "A6_P$8") (pintype "bidirectional"))
      (node (ref "R17") (pin "2") (pinfunction "2_2") (pintype "passive"))
      (node (ref "X3") (pin "2") (pinfunction "KL_2") (pintype "passive"))
    )
    (net (code "70") (name "TX2") (class "Default")
      (node (ref "IC3") (pin "5") (pinfunction "RXD_5") (pintype "input"))
      (node (ref "U$1") (pin "16") (pinfunction "16(TX2)_16") (pintype "bidirectional"))
    )
    (net (code "71") (name "TXN") (class "Default")
      (node (ref "R25") (pin "1") (pinfunction "1_1") (pintype "passive"))
      (node (ref "U1") (pin "1") (pinfunction "TXN_1") (pintype "passive"))
      (node (ref "X9") (pin "2") (pinfunction "TD-_2") (pintype "input"))
    )
    (net (code "72") (name "TXP") (class "Default")
      (node (ref "R24") (pin "1") (pinfunction "1_1") (pintype "passive"))
      (node (ref "U1") (pin "2") (pinfunction "TXP_2") (pintype "passive"))
      (node (ref "X9") (pin "1") (pinfunction "TD+_1") (pintype "input"))
    )
    (net (code "73") (name "USBDM") (class "Default")
      (node (ref "IC3") (pin "16") (pinfunction "USBDM_16") (pintype "bidirectional"))
      (node (ref "X13") (pin "2") (pinfunction "2_2") (pintype "passive"))
    )
    (net (code "74") (name "USBDP") (class "Default")
      (node (ref "IC3") (pin "15") (pinfunction "USBDP_15") (pintype "bidirectional"))
      (node (ref "X13") (pin "3") (pinfunction "3_3") (pintype "passive"))
    )
    (net (code "75") (name "USB_VCC") (class "Default")
      (node (ref "X13") (pin "1") (pinfunction "1_1") (pintype "passive"))
    )
    (net (code "76") (name "VCC") (class "Default")
      (node (ref "C6") (pin "1") (pinfunction "1_1") (pintype "passive"))
      (node (ref "C7") (pin "1") (pinfunction "1_1") (pintype "passive"))
      (node (ref "IC3") (pin "20") (pinfunction "VCC_20") (pintype "power_in"))
      (node (ref "IC6") (pin "P$1") (pinfunction "DIR_P$1") (pintype "input"))
      (node (ref "IC6") (pin "P$20") (pinfunction "VDD_P$20") (pintype "power_in"))
      (node (ref "R12") (pin "2") (pinfunction "2_2") (pintype "passive"))
      (node (ref "R13") (pin "2") (pinfunction "2_2") (pintype "passive"))
      (node (ref "R14") (pin "1") (pinfunction "1_1") (pintype "passive"))
      (node (ref "R15") (pin "1") (pinfunction "1_1") (pintype "passive"))
      (node (ref "R16") (pin "1") (pinfunction "1_1") (pintype "passive"))
      (node (ref "R17") (pin "1") (pinfunction "1_1") (pintype "passive"))
      (node (ref "R18") (pin "1") (pinfunction "1_1") (pintype "passive"))
      (node (ref "R19") (pin "1") (pinfunction "1_1") (pintype "passive"))
      (node (ref "R20") (pin "2") (pinfunction "2_2") (pintype "passive"))
      (node (ref "R21") (pin "1") (pinfunction "1_1") (pintype "passive"))
      (node (ref "R4") (pin "2") (pinfunction "2_2") (pintype "passive"))
      (node (ref "U$1") (pin "+5V@1") (pinfunction "+5V_+5V@1") (pintype "power_in"))
      (node (ref "U$1") (pin "+5V@3") (pinfunction "+5V_+5V@3") (pintype "power_in"))
      (node (ref "U$1") (pin "+5V@4") (pinfunction "+5V_+5V@4") (pintype "power_in"))
      (node (ref "X10") (pin "1") (pinfunction "KL_1") (pintype "passive"))
      (node (ref "X10") (pin "3") (pinfunction "KL_3") (pintype "passive"))
      (node (ref "X2") (pin "2") (pinfunction "KL_2") (pintype "passive"))
    )
    (net (code "77") (name "VPIN") (class "Default")
      (node (ref "R2") (pin "1") (pinfunction "1_1") (pintype "passive"))
      (node (ref "R6") (pin "2") (pinfunction "2_2") (pintype "passive"))
      (node (ref "U$1") (pin "A0") (pinfunction "A0_A0") (pintype "bidirectional"))
    )
    (net (code "78") (name "XBEE_DIN") (class "Default")
      (node (ref "U$1") (pin "18") (pinfunction "18(TX1)_18") (pintype "bidirectional"))
      (node (ref "XB1") (pin "3") (pinfunction "DIN/~{CONFIG}_3") (pintype "input"))
    )
    (net (code "79") (name "XBEE_DOUT") (class "Default")
      (node (ref "U$1") (pin "19") (pinfunction "19(RX1)_19") (pintype "bidirectional"))
      (node (ref "XB1") (pin "2") (pinfunction "DOUT_2") (pintype "output"))
    )
    (net (code "80") (name "XBEE_RESET") (class "Default")
      (node (ref "U$1") (pin "8") (pinfunction "8_8") (pintype "bidirectional"))
      (node (ref "XB1") (pin "5") (pinfunction "~{RESET}_5") (pintype "input"))
    )
    (net (code "81") (name "XI") (class "Default")
      (node (ref "25MHZ") (pin "3") (pinfunction "FO_3") (pintype "output"))
      (node (ref "U1") (pin "30") (pinfunction "XI/CLKIN_30") (pintype "passive"))
    )
    (net (code "82") (name "XO") (class "Default")
      (node (ref "U1") (pin "31") (pinfunction "XO_31") (pintype "passive"))
    )
    (net (code "83") (name "unconnected-(IC1-WP-Pad7)") (class "Default")
      (node (ref "IC1") (pin "7") (pinfunction "WP_7") (pintype "input"))
    )
    (net (code "84") (name "unconnected-(IC3-CBUS0-Pad23)") (class "Default")
      (node (ref "IC3") (pin "23") (pinfunction "CBUS0_23") (pintype "bidirectional"))
    )
    (net (code "85") (name "unconnected-(IC3-CBUS1-Pad22)") (class "Default")
      (node (ref "IC3") (pin "22") (pinfunction "CBUS1_22") (pintype "bidirectional"))
    )
    (net (code "86") (name "unconnected-(IC3-CBUS2-Pad13)") (class "Default")
      (node (ref "IC3") (pin "13") (pinfunction "CBUS2_13") (pintype "bidirectional"))
    )
    (net (code "87") (name "unconnected-(IC3-CBUS3-Pad14)") (class "Default")
      (node (ref "IC3") (pin "14") (pinfunction "CBUS3_14") (pintype "bidirectional"))
    )
    (net (code "88") (name "unconnected-(IC3-CBUS4-Pad12)") (class "Default")
      (node (ref "IC3") (pin "12") (pinfunction "CBUS4_12") (pintype "bidirectional"))
    )
    (net (code "89") (name "unconnected-(IC3-OSCI-Pad27)") (class "Default")
      (node (ref "IC3") (pin "27") (pinfunction "OSCI_27") (pintype "input"))
    )
    (net (code "90") (name "unconnected-(IC3-OSCO-Pad28)") (class "Default")
      (node (ref "IC3") (pin "28") (pinfunction "OSCO_28") (pintype "output"))
    )
    (net (code "91") (name "unconnected-(IC3-TEST-Pad26)") (class "Default")
      (node (ref "IC3") (pin "26") (pinfunction "TEST_26") (pintype "input"))
    )
    (net (code "92") (name "unconnected-(IC3-~{RI}-Pad6)") (class "Default")
      (node (ref "IC3") (pin "6") (pinfunction "~{RI}_6") (pintype "input"))
    )
    (net (code "93") (name "unconnected-(IC5A-B4-PadP$14)") (class "Default")
      (node (ref "IC5") (pin "P$14") (pinfunction "B4_P$14") (pintype "bidirectional"))
    )
    (net (code "94") (name "unconnected-(IC6A-B4-PadP$14)") (class "Default")
      (node (ref "IC6") (pin "P$14") (pinfunction "B4_P$14") (pintype "bidirectional"))
    )
    (net (code "95") (name "unconnected-(IC6A-B5-PadP$13)") (class "Default")
      (node (ref "IC6") (pin "P$13") (pinfunction "B5_P$13") (pintype "bidirectional"))
    )
    (net (code "96") (name "unconnected-(IC6A-B6-PadP$12)") (class "Default")
      (node (ref "IC6") (pin "P$12") (pinfunction "B6_P$12") (pintype "bidirectional"))
    )
    (net (code "97") (name "unconnected-(IC6A-B7-PadP$11)") (class "Default")
      (node (ref "IC6") (pin "P$11") (pinfunction "B7_P$11") (pintype "bidirectional"))
    )
    (net (code "98") (name "unconnected-(J2-Pad3)") (class "Default")
      (node (ref "J2") (pin "3") (pinfunction "3_3") (pintype "bidirectional"))
    )
    (net (code "99") (name "unconnected-(J2-Pad4)") (class "Default")
      (node (ref "J2") (pin "4") (pinfunction "4_4") (pintype "bidirectional"))
    )
    (net (code "100") (name "unconnected-(U$1-(N{slash}C)-PadN{slash}C)") (class "Default")
      (node (ref "U$1") (pin "N/C") (pinfunction "(N/C)_N/C") (pintype "no_connect"))
    )
    (net (code "101") (name "unconnected-(U$1-0(RX)-Pad0)") (class "Default")
      (node (ref "U$1") (pin "0") (pinfunction "0(RX)_0") (pintype "bidirectional"))
    )
    (net (code "102") (name "unconnected-(U$1-1(TX)-Pad1)") (class "Default")
      (node (ref "U$1") (pin "1") (pinfunction "1(TX)_1") (pintype "bidirectional"))
    )
    (net (code "103") (name "unconnected-(U$1-14(TX3)-Pad14)") (class "Default")
      (node (ref "U$1") (pin "14") (pinfunction "14(TX3)_14") (pintype "bidirectional"))
    )
    (net (code "104") (name "unconnected-(U$1-15(RX3)-Pad15)") (class "Default")
      (node (ref "U$1") (pin "15") (pinfunction "15(RX3)_15") (pintype "bidirectional"))
    )
    (net (code "105") (name "unconnected-(U$1-20(SDA)-Pad20)") (class "Default")
      (node (ref "U$1") (pin "20") (pinfunction "20(SDA)_20") (pintype "bidirectional"))
    )
    (net (code "106") (name "unconnected-(U$1-21(SCL)-Pad21)") (class "Default")
      (node (ref "U$1") (pin "21") (pinfunction "21(SCL)_21") (pintype "bidirectional"))
    )
    (net (code "107") (name "unconnected-(U$1-CANRX-PadA14)") (class "Default")
      (node (ref "U$1") (pin "A14") (pinfunction "CANRX_A14") (pintype "bidirectional"))
    )
    (net (code "108") (name "unconnected-(U$1-CANTX-PadA15)") (class "Default")
      (node (ref "U$1") (pin "A15") (pinfunction "CANTX_A15") (pintype "bidirectional"))
    )
    (net (code "109") (name "unconnected-(U$1-DAC0-PadA12)") (class "Default")
      (node (ref "U$1") (pin "A12") (pinfunction "DAC0_A12") (pintype "bidirectional"))
    )
    (net (code "110") (name "unconnected-(U$1-DAC1-PadA13)") (class "Default")
      (node (ref "U$1") (pin "A13") (pinfunction "DAC1_A13") (pintype "bidirectional"))
    )
    (net (code "111") (name "unconnected-(U$1-IOREF-PadI{slash}OREF)") (class "Default")
      (node (ref "U$1") (pin "I/OREF") (pinfunction "IOREF_I/OREF") (pintype "bidirectional"))
    )
    (net (code "112") (name "unconnected-(U$1-Pad4)") (class "Default")
      (node (ref "U$1") (pin "4") (pinfunction "4_4") (pintype "bidirectional"))
    )
    (net (code "113") (name "unconnected-(U$1-Pad9)") (class "Default")
      (node (ref "U$1") (pin "9") (pinfunction "9_9") (pintype "bidirectional"))
    )
    (net (code "114") (name "unconnected-(U$1-Pad22)") (class "Default")
      (node (ref "U$1") (pin "22") (pinfunction "22_22") (pintype "bidirectional"))
    )
    (net (code "115") (name "unconnected-(U$1-Pad24)") (class "Default")
      (node (ref "U$1") (pin "24") (pinfunction "24_24") (pintype "bidirectional"))
    )
    (net (code "116") (name "unconnected-(U$1-Pad25)") (class "Default")
      (node (ref "U$1") (pin "25") (pinfunction "25_25") (pintype "bidirectional"))
    )
    (net (code "117") (name "unconnected-(U$1-Pad26)") (class "Default")
      (node (ref "U$1") (pin "26") (pinfunction "26_26") (pintype "bidirectional"))
    )
    (net (code "118") (name "unconnected-(U$1-Pad27)") (class "Default")
      (node (ref "U$1") (pin "27") (pinfunction "27_27") (pintype "bidirectional"))
    )
    (net (code "119") (name "unconnected-(U$1-Pad28)") (class "Default")
      (node (ref "U$1") (pin "28") (pinfunction "28_28") (pintype "bidirectional"))
    )
    (net (code "120") (name "unconnected-(U$1-Pad29)") (class "Default")
      (node (ref "U$1") (pin "29") (pinfunction "29_29") (pintype "bidirectional"))
    )
    (net (code "121") (name "unconnected-(U$1-Pad30)") (class "Default")
      (node (ref "U$1") (pin "30") (pinfunction "30_30") (pintype "bidirectional"))
    )
    (net (code "122") (name "unconnected-(U$1-Pad31)") (class "Default")
      (node (ref "U$1") (pin "31") (pinfunction "31_31") (pintype "bidirectional"))
    )
    (net (code "123") (name "unconnected-(U$1-Pad33)") (class "Default")
      (node (ref "U$1") (pin "33") (pinfunction "33_33") (pintype "bidirectional"))
    )
    (net (code "124") (name "unconnected-(U$1-Pad34)") (class "Default")
      (node (ref "U$1") (pin "34") (pinfunction "34_34") (pintype "bidirectional"))
    )
    (net (code "125") (name "unconnected-(U$1-Pad35)") (class "Default")
      (node (ref "U$1") (pin "35") (pinfunction "35_35") (pintype "bidirectional"))
    )
    (net (code "126") (name "unconnected-(U$1-Pad36)") (class "Default")
      (node (ref "U$1") (pin "36") (pinfunction "36_36") (pintype "bidirectional"))
    )
    (net (code "127") (name "unconnected-(U$1-Pad37)") (class "Default")
      (node (ref "U$1") (pin "37") (pinfunction "37_37") (pintype "bidirectional"))
    )
    (net (code "128") (name "unconnected-(U$1-Pad38)") (class "Default")
      (node (ref "U$1") (pin "38") (pinfunction "38_38") (pintype "bidirectional"))
    )
    (net (code "129") (name "unconnected-(U$1-Pad39)") (class "Default")
      (node (ref "U$1") (pin "39") (pinfunction "39_39") (pintype "bidirectional"))
    )
    (net (code "130") (name "unconnected-(U$1-Pad40)") (class "Default")
      (node (ref "U$1") (pin "40") (pinfunction "40_40") (pintype "bidirectional"))
    )
    (net (code "131") (name "unconnected-(U$1-Pad41)") (class "Default")
      (node (ref "U$1") (pin "41") (pinfunction "41_41") (pintype "bidirectional"))
    )
    (net (code "132") (name "unconnected-(U$1-Pad42)") (class "Default")
      (node (ref "U$1") (pin "42") (pinfunction "42_42") (pintype "bidirectional"))
    )
    (net (code "133") (name "unconnected-(U$1-Pad43)") (class "Default")
      (node (ref "U$1") (pin "43") (pinfunction "43_43") (pintype "bidirectional"))
    )
    (net (code "134") (name "unconnected-(U$1-Pad44)") (class "Default")
      (node (ref "U$1") (pin "44") (pinfunction "44_44") (pintype "bidirectional"))
    )
    (net (code "135") (name "unconnected-(U$1-Pad45)") (class "Default")
      (node (ref "U$1") (pin "45") (pinfunction "45_45") (pintype "bidirectional"))
    )
    (net (code "136") (name "unconnected-(U$1-Pad46)") (class "Default")
      (node (ref "U$1") (pin "46") (pinfunction "46_46") (pintype "bidirectional"))
    )
    (net (code "137") (name "unconnected-(U$1-Pad47)") (class "Default")
      (node (ref "U$1") (pin "47") (pinfunction "47_47") (pintype "bidirectional"))
    )
    (net (code "138") (name "unconnected-(U$1-Pad48)") (class "Default")
      (node (ref "U$1") (pin "48") (pinfunction "48_48") (pintype "bidirectional"))
    )
    (net (code "139") (name "unconnected-(U$1-Pad49)") (class "Default")
      (node (ref "U$1") (pin "49") (pinfunction "49_49") (pintype "bidirectional"))
    )
    (net (code "140") (name "unconnected-(U$1-Pad50)") (class "Default")
      (node (ref "U$1") (pin "50") (pinfunction "50_50") (pintype "bidirectional"))
    )
    (net (code "141") (name "unconnected-(U$1-Pad51)") (class "Default")
      (node (ref "U$1") (pin "51") (pinfunction "51_51") (pintype "bidirectional"))
    )
    (net (code "142") (name "unconnected-(U$1-PadA1)") (class "Default")
      (node (ref "U$1") (pin "A1") (pinfunction "A1_A1") (pintype "bidirectional"))
    )
    (net (code "143") (name "unconnected-(U$1-PadA2)") (class "Default")
      (node (ref "U$1") (pin "A2") (pinfunction "A2_A2") (pintype "bidirectional"))
    )
    (net (code "144") (name "unconnected-(U$1-PadA3)") (class "Default")
      (node (ref "U$1") (pin "A3") (pinfunction "A3_A3") (pintype "bidirectional"))
    )
    (net (code "145") (name "unconnected-(U$1-PadA6)") (class "Default")
      (node (ref "U$1") (pin "A6") (pinfunction "A6_A6") (pintype "bidirectional"))
    )
    (net (code "146") (name "unconnected-(U$1-PadA7)") (class "Default")
      (node (ref "U$1") (pin "A7") (pinfunction "A7_A7") (pintype "bidirectional"))
    )
    (net (code "147") (name "unconnected-(U$1-PadA8)") (class "Default")
      (node (ref "U$1") (pin "A8") (pinfunction "A8_A8") (pintype "bidirectional"))
    )
    (net (code "148") (name "unconnected-(U$1-PadA9)") (class "Default")
      (node (ref "U$1") (pin "A9") (pinfunction "A9_A9") (pintype "bidirectional"))
    )
    (net (code "149") (name "unconnected-(U$1-PadA10)") (class "Default")
      (node (ref "U$1") (pin "A10") (pinfunction "A10_A10") (pintype "bidirectional"))
    )
    (net (code "150") (name "unconnected-(U$1-PadA11)") (class "Default")
      (node (ref "U$1") (pin "A11") (pinfunction "A11_A11") (pintype "bidirectional"))
    )
    (net (code "151") (name "unconnected-(U$1-PadAREF)") (class "Default")
      (node (ref "U$1") (pin "AREF") (pinfunction "AREF_AREF") (pintype "bidirectional"))
    )
    (net (code "152") (name "unconnected-(U$1-PadRESET.)") (class "Default")
      (node (ref "U$1") (pin "RESET.") (pinfunction "RESET._RESET.") (pintype "bidirectional"))
    )
    (net (code "153") (name "unconnected-(U1-DNC-Pad7)") (class "Default")
      (node (ref "U1") (pin "7") (pinfunction "DNC_7") (pintype "passive"))
    )
    (net (code "154") (name "unconnected-(U1-DUPLED-Pad26)") (class "Default")
      (node (ref "U1") (pin "26") (pinfunction "DUPLED_26") (pintype "passive"))
    )
    (net (code "155") (name "unconnected-(U1-NC-Pad12)") (class "Default")
      (node (ref "U1") (pin "12") (pinfunction "NC_12") (pintype "passive"))
    )
    (net (code "156") (name "unconnected-(U1-NC-Pad13)") (class "Default")
      (node (ref "U1") (pin "13") (pinfunction "NC_13") (pintype "passive"))
    )
    (net (code "157") (name "unconnected-(U1-NC-Pad46)") (class "Default")
      (node (ref "U1") (pin "46") (pinfunction "NC_46") (pintype "passive"))
    )
    (net (code "158") (name "unconnected-(U1-NC-Pad47)") (class "Default")
      (node (ref "U1") (pin "47") (pinfunction "NC_47") (pintype "passive"))
    )
    (net (code "159") (name "unconnected-(U1-SPDLED-Pad24)") (class "Default")
      (node (ref "U1") (pin "24") (pinfunction "SPDLED_24") (pintype "passive"))
    )
    (net (code "160") (name "unconnected-(U1-VBG-Pad18)") (class "Default")
      (node (ref "U1") (pin "18") (pinfunction "VBG_18") (pintype "passive"))
    )
    (net (code "161") (name "unconnected-(XB1-AD0{slash}DIO0-Pad20)") (class "Default")
      (node (ref "XB1") (pin "20") (pinfunction "AD0/DIO0_20") (pintype "bidirectional"))
    )
    (net (code "162") (name "unconnected-(XB1-AD1{slash}DIO1-Pad19)") (class "Default")
      (node (ref "XB1") (pin "19") (pinfunction "AD1/DIO1_19") (pintype "bidirectional"))
    )
    (net (code "163") (name "unconnected-(XB1-AD2{slash}DIO2-Pad18)") (class "Default")
      (node (ref "XB1") (pin "18") (pinfunction "AD2/DIO2_18") (pintype "bidirectional"))
    )
    (net (code "164") (name "unconnected-(XB1-ASSOC{slash}AD5{slash}DIO5-Pad15)") (class "Default")
      (node (ref "XB1") (pin "15") (pinfunction "ASSOC/AD5/DIO5_15") (pintype "bidirectional"))
    )
    (net (code "165") (name "unconnected-(XB1-CD{slash}DOUT_EN{slash}DO8-Pad4)") (class "Default")
      (node (ref "XB1") (pin "4") (pinfunction "CD/DOUT_EN/DO8_4") (pintype "output"))
    )
    (net (code "166") (name "unconnected-(XB1-COORD_SEL{slash}AD3{slash}DIO3-Pad17)") (class "Default")
      (node (ref "XB1") (pin "17") (pinfunction "COORD_SEL/AD3/DIO3_17") (pintype "bidirectional"))
    )
    (net (code "167") (name "unconnected-(XB1-ON{slash}~{SLEEP}-Pad13)") (class "Default")
      (node (ref "XB1") (pin "13") (pinfunction "ON/~{SLEEP}_13") (pintype "output"))
    )
    (net (code "168") (name "unconnected-(XB1-PWM0{slash}RSSI-Pad6)") (class "Default")
      (node (ref "XB1") (pin "6") (pinfunction "PWM0/RSSI_6") (pintype "output"))
    )
    (net (code "169") (name "unconnected-(XB1-RF_TX{slash}AD4{slash}DIO4-Pad11)") (class "Default")
      (node (ref "XB1") (pin "11") (pinfunction "RF_TX/AD4/DIO4_11") (pintype "bidirectional"))
    )
    (net (code "170") (name "unconnected-(XB1-VREF-Pad14)") (class "Default")
      (node (ref "XB1") (pin "14") (pinfunction "VREF_14") (pintype "input"))
    )
  )
)
